# AMU-S04-V00-Microcontroller.net
KiCad netlist of a schematic drawn in Altium Designer
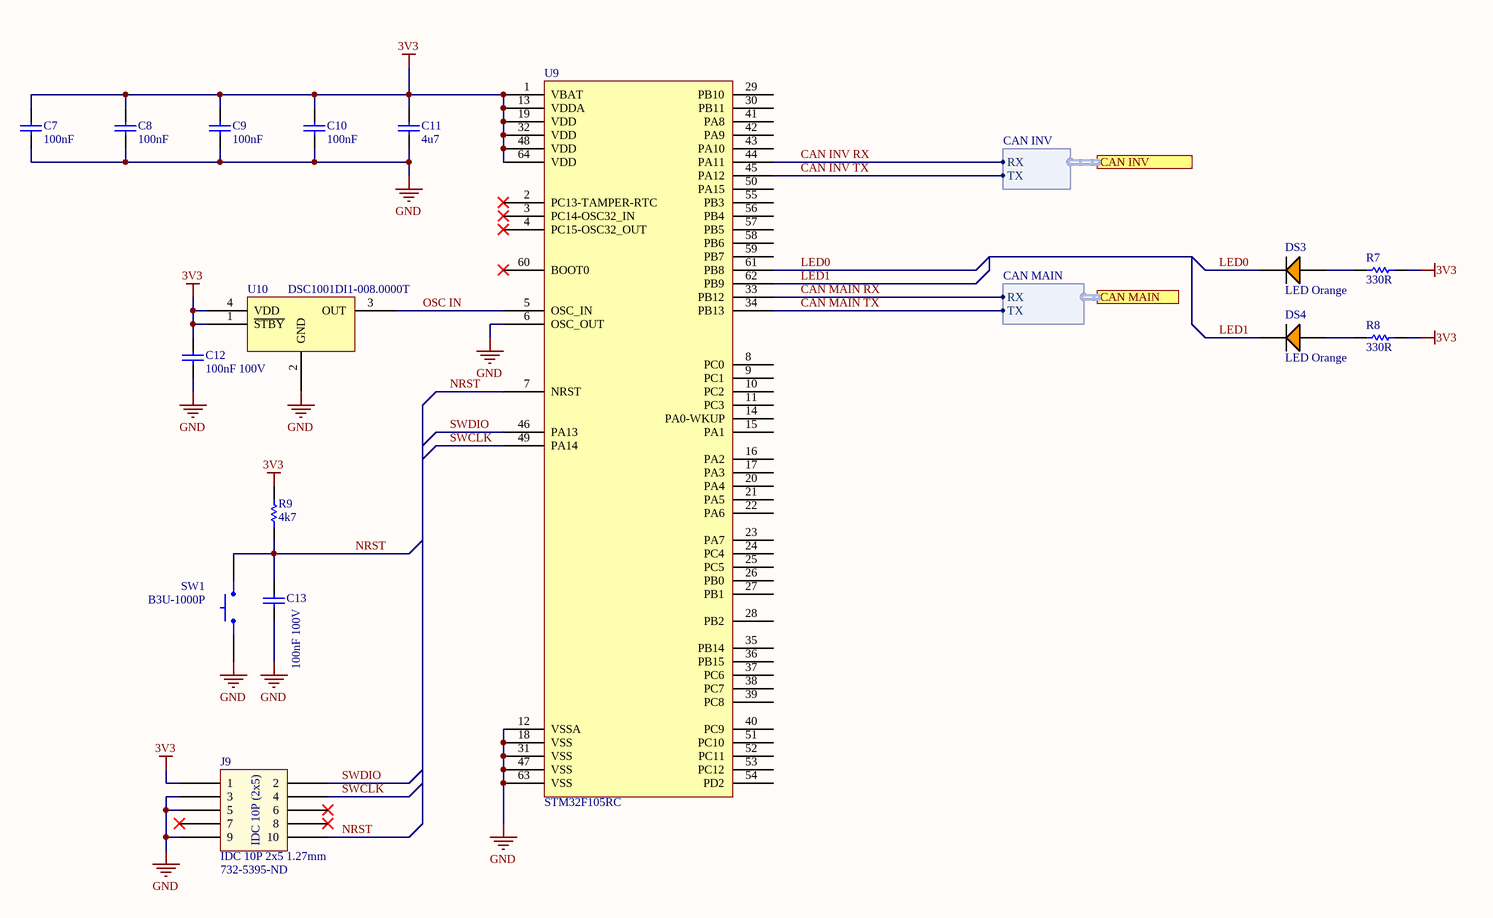
[diagram p0: AMU-S04-V00-Microcontroller.SchDoc]

(export (version "E")
  (design (tool "Eeschema 10.0.6"))
  (components
    (comp (ref "C7")
      (value "100nF")
      (footprint "Cap_Ceramic_0603")
      (description "Capacitor, Ceramic, SMD, 100nF, 50V, 5%, X7R, 0603")
      (libsource (lib "StandardCapacitors") (part "100nF 50V 5% X7R 0603"))
    )
    (comp (ref "C8")
      (value "100nF")
      (footprint "Cap_Ceramic_0603")
      (description "Capacitor, Ceramic, SMD, 100nF, 50V, 5%, X7R, 0603")
      (libsource (lib "StandardCapacitors") (part "100nF 50V 5% X7R 0603"))
    )
    (comp (ref "C9")
      (value "100nF")
      (footprint "Cap_Ceramic_0603")
      (description "Capacitor, Ceramic, SMD, 100nF, 50V, 5%, X7R, 0603")
      (libsource (lib "StandardCapacitors") (part "100nF 50V 5% X7R 0603"))
    )
    (comp (ref "C10")
      (value "100nF")
      (footprint "Cap_Ceramic_0603")
      (description "Capacitor, Ceramic, SMD, 100nF, 50V, 5%, X7R, 0603")
      (libsource (lib "StandardCapacitors") (part "100nF 50V 5% X7R 0603"))
    )
    (comp (ref "C11")
      (value "4u7")
      (footprint "Cap_Ceramic_0603")
      (description "Capacitor, Ceramic, SMD, 4u7, 50V, 5%, X7R, 0603")
      (libsource (lib "StandardCapacitors") (part "4u7 50V 5% X7R 0603"))
    )
    (comp (ref "C12")
      (value "100nF 100V")
      (footprint "Cap_Ceramic_0603")
      (description "Capacitor, Ceramic, SMD, 100nF, 100V, 5%, X7R, 0603")
      (libsource (lib "StandardCapacitors") (part "100nF 100V 5% X7R 0603"))
    )
    (comp (ref "C13")
      (value "100nF 100V")
      (footprint "Cap_Ceramic_0603")
      (description "Capacitor, Ceramic, SMD, 100nF, 100V, 5%, X7R, 0603")
      (libsource (lib "StandardCapacitors") (part "100nF 100V 5% X7R 0603"))
    )
    (comp (ref "DS3")
      (value "LED Orange")
      (footprint "LED ORANGE 0603")
      (libsource (lib "QUTMS_LEDLibrary") (part "LED ORANGE 0603"))
    )
    (comp (ref "DS4")
      (value "LED Orange")
      (footprint "LED ORANGE 0603")
      (libsource (lib "QUTMS_LEDLibrary") (part "LED ORANGE 0603"))
    )
    (comp (ref "J9")
      (value "IDC 10P 2x5 1.27mm")
      (footprint "IDC 1.27MM 10P")
      (libsource (lib "IDCConnectors") (part "IDC 10P 2x5 1.27mm"))
    )
    (comp (ref "R7")
      (value "330R")
      (footprint "Res_ThinFilm_0603")
      (description "Resistor, SMD, 330R, 0.1W, 5%, 0603")
      (libsource (lib "StandardResistors") (part "330R 5% 0603"))
    )
    (comp (ref "R8")
      (value "330R")
      (footprint "Res_ThinFilm_0603")
      (description "Resistor, SMD, 330R, 0.1W, 5%, 0603")
      (libsource (lib "StandardResistors") (part "330R 5% 0603"))
    )
    (comp (ref "R9")
      (value "4k7")
      (footprint "Res_ThinFilm_0603")
      (description "Resistor, SMD, 4k7, 0.1W, 5%, 0603")
      (libsource (lib "StandardResistors") (part "4k7 5% 0603"))
    )
    (comp (ref "SW1")
      (value "B3U-1000P")
      (footprint "BTN B3U-1000P")
      (description "Omron B3U-1000P Ultra Miniture Switch")
      (libsource (lib "QUTMS_SwitchLibrary") (part "BTN B3U-1000P"))
    )
    (comp (ref "U9")
      (value "STM32F105RC")
      (footprint "STM32F105RC")
      (description "ARM® Cortex®-M3 STM32F1 Microcontroller IC 32-Bit 72MHz 256KB (256K x 8) FLASH 64-LQFP (10x10)")
      (libsource (lib "QUTMS_STM32Library") (part "STM32F105RC"))
    )
    (comp (ref "U10")
      (value "DSC1001DI1-008.0000T")
      (footprint "DSC1001DI1-008.0000TCT-ND")
      (description "on 8MHz XO (Standard) CMOS Oscillator 1.8 ~ 3.3V Standby (Power Down) 4-SMD, No Lead")
      (libsource (lib "QUTMS_CrystalLibrary") (part "DSC1001DI1-008.0000T"))
    )
  )
  (nets
    (net (code "4") (name "/CAN INV RX") (class "Default")
      (node (ref "U9") (pin "44") (pinfunction "PA11_44") (pintype "passive"))
    )
    (net (code "5") (name "/CAN INV TX") (class "Default")
      (node (ref "U9") (pin "45") (pinfunction "PA12_45") (pintype "passive"))
    )
    (net (code "6") (name "/CAN MAIN RX") (class "Default")
      (node (ref "U9") (pin "33") (pinfunction "PB12_33") (pintype "passive"))
    )
    (net (code "7") (name "/CAN MAIN TX") (class "Default")
      (node (ref "U9") (pin "34") (pinfunction "PB13_34") (pintype "passive"))
    )
    (net (code "8") (name "/LED0") (class "Default")
      (node (ref "DS3") (pin "2") (pinfunction "C_2") (pintype "passive"))
      (node (ref "U9") (pin "61") (pinfunction "PB8_61") (pintype "passive"))
    )
    (net (code "9") (name "/LED1") (class "Default")
      (node (ref "DS4") (pin "2") (pinfunction "C_2") (pintype "passive"))
      (node (ref "U9") (pin "62") (pinfunction "PB9_62") (pintype "passive"))
    )
    (net (code "10") (name "/NRST") (class "Default")
      (node (ref "C13") (pin "2") (pinfunction "2_2") (pintype "passive"))
      (node (ref "J9") (pin "10") (pinfunction "10_10") (pintype "passive"))
      (node (ref "R9") (pin "1") (pinfunction "1_1") (pintype "passive"))
      (node (ref "SW1") (pin "2") (pinfunction "2_2") (pintype "passive"))
      (node (ref "U9") (pin "7") (pinfunction "NRST_7") (pintype "passive"))
    )
    (net (code "11") (name "/OSC IN") (class "Default")
      (node (ref "U10") (pin "3") (pinfunction "OUT_3") (pintype "passive"))
      (node (ref "U9") (pin "5") (pinfunction "OSC_IN_5") (pintype "passive"))
    )
    (net (code "12") (name "/SWCLK") (class "Default")
      (node (ref "J9") (pin "4") (pinfunction "4_4") (pintype "passive"))
      (node (ref "U9") (pin "49") (pinfunction "PA14_49") (pintype "passive"))
    )
    (net (code "13") (name "/SWDIO") (class "Default")
      (node (ref "J9") (pin "2") (pinfunction "2_2") (pintype "passive"))
      (node (ref "U9") (pin "46") (pinfunction "PA13_46") (pintype "passive"))
    )
    (net (code "16") (name "3V3") (class "Default")
      (node (ref "C10") (pin "2") (pinfunction "2_2") (pintype "passive"))
      (node (ref "C11") (pin "2") (pinfunction "2_2") (pintype "passive"))
      (node (ref "C12") (pin "2") (pinfunction "2_2") (pintype "passive"))
      (node (ref "C7") (pin "2") (pinfunction "2_2") (pintype "passive"))
      (node (ref "C8") (pin "2") (pinfunction "2_2") (pintype "passive"))
      (node (ref "C9") (pin "2") (pinfunction "2_2") (pintype "passive"))
      (node (ref "J9") (pin "1") (pinfunction "1_1") (pintype "passive"))
      (node (ref "R7") (pin "2") (pinfunction "2_2") (pintype "passive"))
      (node (ref "R8") (pin "2") (pinfunction "2_2") (pintype "passive"))
      (node (ref "R9") (pin "2") (pinfunction "2_2") (pintype "passive"))
      (node (ref "U10") (pin "1") (pinfunction "~{STBY}_1") (pintype "passive"))
      (node (ref "U10") (pin "4") (pinfunction "VDD_4") (pintype "passive"))
      (node (ref "U9") (pin "1") (pinfunction "VBAT_1") (pintype "passive"))
      (node (ref "U9") (pin "13") (pinfunction "VDDA_13") (pintype "passive"))
      (node (ref "U9") (pin "19") (pinfunction "VDD_19") (pintype "passive"))
      (node (ref "U9") (pin "32") (pinfunction "VDD_32") (pintype "passive"))
      (node (ref "U9") (pin "48") (pinfunction "VDD_48") (pintype "passive"))
      (node (ref "U9") (pin "64") (pinfunction "VDD_64") (pintype "passive"))
    )
    (net (code "17") (name "GND") (class "Default")
      (node (ref "C10") (pin "1") (pinfunction "1_1") (pintype "passive"))
      (node (ref "C11") (pin "1") (pinfunction "1_1") (pintype "passive"))
      (node (ref "C12") (pin "1") (pinfunction "1_1") (pintype "passive"))
      (node (ref "C13") (pin "1") (pinfunction "1_1") (pintype "passive"))
      (node (ref "C7") (pin "1") (pinfunction "1_1") (pintype "passive"))
      (node (ref "C8") (pin "1") (pinfunction "1_1") (pintype "passive"))
      (node (ref "C9") (pin "1") (pinfunction "1_1") (pintype "passive"))
      (node (ref "J9") (pin "3") (pinfunction "3_3") (pintype "passive"))
      (node (ref "J9") (pin "5") (pinfunction "5_5") (pintype "passive"))
      (node (ref "J9") (pin "9") (pinfunction "9_9") (pintype "passive"))
      (node (ref "SW1") (pin "1") (pinfunction "1_1") (pintype "passive"))
      (node (ref "U10") (pin "2") (pinfunction "GND_2") (pintype "passive"))
      (node (ref "U9") (pin "12") (pinfunction "VSSA_12") (pintype "passive"))
      (node (ref "U9") (pin "18") (pinfunction "VSS_18") (pintype "passive"))
      (node (ref "U9") (pin "31") (pinfunction "VSS_31") (pintype "passive"))
      (node (ref "U9") (pin "47") (pinfunction "VSS_47") (pintype "passive"))
      (node (ref "U9") (pin "6") (pinfunction "OSC_OUT_6") (pintype "passive"))
      (node (ref "U9") (pin "63") (pinfunction "VSS_63") (pintype "passive"))
    )
    (net (code "18") (name "Net-(DS3-A)") (class "Default")
      (node (ref "DS3") (pin "1") (pinfunction "A_1") (pintype "passive"))
      (node (ref "R7") (pin "1") (pinfunction "1_1") (pintype "passive"))
    )
    (net (code "19") (name "Net-(DS4-A)") (class "Default")
      (node (ref "DS4") (pin "1") (pinfunction "A_1") (pintype "passive"))
      (node (ref "R8") (pin "1") (pinfunction "1_1") (pintype "passive"))
    )
    (net (code "20") (name "unconnected-(J9-Pad6)") (class "Default")
      (node (ref "J9") (pin "6") (pinfunction "6_6") (pintype "passive+no_connect"))
    )
    (net (code "21") (name "unconnected-(J9-Pad7)") (class "Default")
      (node (ref "J9") (pin "7") (pinfunction "7_7") (pintype "passive+no_connect"))
    )
    (net (code "22") (name "unconnected-(J9-Pad8)") (class "Default")
      (node (ref "J9") (pin "8") (pinfunction "8_8") (pintype "passive+no_connect"))
    )
    (net (code "23") (name "unconnected-(U9-BOOT0-Pad60)") (class "Default")
      (node (ref "U9") (pin "60") (pinfunction "BOOT0_60") (pintype "passive+no_connect"))
    )
    (net (code "24") (name "unconnected-(U9-PA0-WKUP-Pad14)") (class "Default")
      (node (ref "U9") (pin "14") (pinfunction "PA0-WKUP_14") (pintype "passive"))
    )
    (net (code "25") (name "unconnected-(U9-PA1-Pad15)") (class "Default")
      (node (ref "U9") (pin "15") (pinfunction "PA1_15") (pintype "passive"))
    )
    (net (code "26") (name "unconnected-(U9-PA2-Pad16)") (class "Default")
      (node (ref "U9") (pin "16") (pinfunction "PA2_16") (pintype "passive"))
    )
    (net (code "27") (name "unconnected-(U9-PA3-Pad17)") (class "Default")
      (node (ref "U9") (pin "17") (pinfunction "PA3_17") (pintype "passive"))
    )
    (net (code "28") (name "unconnected-(U9-PA4-Pad20)") (class "Default")
      (node (ref "U9") (pin "20") (pinfunction "PA4_20") (pintype "passive"))
    )
    (net (code "29") (name "unconnected-(U9-PA5-Pad21)") (class "Default")
      (node (ref "U9") (pin "21") (pinfunction "PA5_21") (pintype "passive"))
    )
    (net (code "30") (name "unconnected-(U9-PA6-Pad22)") (class "Default")
      (node (ref "U9") (pin "22") (pinfunction "PA6_22") (pintype "passive"))
    )
    (net (code "31") (name "unconnected-(U9-PA7-Pad23)") (class "Default")
      (node (ref "U9") (pin "23") (pinfunction "PA7_23") (pintype "passive"))
    )
    (net (code "32") (name "unconnected-(U9-PA8-Pad41)") (class "Default")
      (node (ref "U9") (pin "41") (pinfunction "PA8_41") (pintype "passive"))
    )
    (net (code "33") (name "unconnected-(U9-PA9-Pad42)") (class "Default")
      (node (ref "U9") (pin "42") (pinfunction "PA9_42") (pintype "passive"))
    )
    (net (code "34") (name "unconnected-(U9-PA10-Pad43)") (class "Default")
      (node (ref "U9") (pin "43") (pinfunction "PA10_43") (pintype "passive"))
    )
    (net (code "35") (name "unconnected-(U9-PA15-Pad50)") (class "Default")
      (node (ref "U9") (pin "50") (pinfunction "PA15_50") (pintype "passive"))
    )
    (net (code "36") (name "unconnected-(U9-PB0-Pad26)") (class "Default")
      (node (ref "U9") (pin "26") (pinfunction "PB0_26") (pintype "passive"))
    )
    (net (code "37") (name "unconnected-(U9-PB1-Pad27)") (class "Default")
      (node (ref "U9") (pin "27") (pinfunction "PB1_27") (pintype "passive"))
    )
    (net (code "38") (name "unconnected-(U9-PB2-Pad28)") (class "Default")
      (node (ref "U9") (pin "28") (pinfunction "PB2_28") (pintype "passive"))
    )
    (net (code "39") (name "unconnected-(U9-PB3-Pad55)") (class "Default")
      (node (ref "U9") (pin "55") (pinfunction "PB3_55") (pintype "passive"))
    )
    (net (code "40") (name "unconnected-(U9-PB4-Pad56)") (class "Default")
      (node (ref "U9") (pin "56") (pinfunction "PB4_56") (pintype "passive"))
    )
    (net (code "41") (name "unconnected-(U9-PB5-Pad57)") (class "Default")
      (node (ref "U9") (pin "57") (pinfunction "PB5_57") (pintype "passive"))
    )
    (net (code "42") (name "unconnected-(U9-PB6-Pad58)") (class "Default")
      (node (ref "U9") (pin "58") (pinfunction "PB6_58") (pintype "passive"))
    )
    (net (code "43") (name "unconnected-(U9-PB7-Pad59)") (class "Default")
      (node (ref "U9") (pin "59") (pinfunction "PB7_59") (pintype "passive"))
    )
    (net (code "44") (name "unconnected-(U9-PB10-Pad29)") (class "Default")
      (node (ref "U9") (pin "29") (pinfunction "PB10_29") (pintype "passive"))
    )
    (net (code "45") (name "unconnected-(U9-PB11-Pad30)") (class "Default")
      (node (ref "U9") (pin "30") (pinfunction "PB11_30") (pintype "passive"))
    )
    (net (code "46") (name "unconnected-(U9-PB14-Pad35)") (class "Default")
      (node (ref "U9") (pin "35") (pinfunction "PB14_35") (pintype "passive"))
    )
    (net (code "47") (name "unconnected-(U9-PB15-Pad36)") (class "Default")
      (node (ref "U9") (pin "36") (pinfunction "PB15_36") (pintype "passive"))
    )
    (net (code "48") (name "unconnected-(U9-PC0-Pad8)") (class "Default")
      (node (ref "U9") (pin "8") (pinfunction "PC0_8") (pintype "passive"))
    )
    (net (code "49") (name "unconnected-(U9-PC1-Pad9)") (class "Default")
      (node (ref "U9") (pin "9") (pinfunction "PC1_9") (pintype "passive"))
    )
    (net (code "50") (name "unconnected-(U9-PC2-Pad10)") (class "Default")
      (node (ref "U9") (pin "10") (pinfunction "PC2_10") (pintype "passive"))
    )
    (net (code "51") (name "unconnected-(U9-PC3-Pad11)") (class "Default")
      (node (ref "U9") (pin "11") (pinfunction "PC3_11") (pintype "passive"))
    )
    (net (code "52") (name "unconnected-(U9-PC4-Pad24)") (class "Default")
      (node (ref "U9") (pin "24") (pinfunction "PC4_24") (pintype "passive"))
    )
    (net (code "53") (name "unconnected-(U9-PC5-Pad25)") (class "Default")
      (node (ref "U9") (pin "25") (pinfunction "PC5_25") (pintype "passive"))
    )
    (net (code "54") (name "unconnected-(U9-PC6-Pad37)") (class "Default")
      (node (ref "U9") (pin "37") (pinfunction "PC6_37") (pintype "passive"))
    )
    (net (code "55") (name "unconnected-(U9-PC7-Pad38)") (class "Default")
      (node (ref "U9") (pin "38") (pinfunction "PC7_38") (pintype "passive"))
    )
    (net (code "56") (name "unconnected-(U9-PC8-Pad39)") (class "Default")
      (node (ref "U9") (pin "39") (pinfunction "PC8_39") (pintype "passive"))
    )
    (net (code "57") (name "unconnected-(U9-PC9-Pad40)") (class "Default")
      (node (ref "U9") (pin "40") (pinfunction "PC9_40") (pintype "passive"))
    )
    (net (code "58") (name "unconnected-(U9-PC10-Pad51)") (class "Default")
      (node (ref "U9") (pin "51") (pinfunction "PC10_51") (pintype "passive"))
    )
    (net (code "59") (name "unconnected-(U9-PC11-Pad52)") (class "Default")
      (node (ref "U9") (pin "52") (pinfunction "PC11_52") (pintype "passive"))
    )
    (net (code "60") (name "unconnected-(U9-PC12-Pad53)") (class "Default")
      (node (ref "U9") (pin "53") (pinfunction "PC12_53") (pintype "passive"))
    )
    (net (code "61") (name "unconnected-(U9-PC13-TAMPER-RTC-Pad2)") (class "Default")
      (node (ref "U9") (pin "2") (pinfunction "PC13-TAMPER-RTC_2") (pintype "passive+no_connect"))
    )
    (net (code "62") (name "unconnected-(U9-PC14-OSC32_IN-Pad3)") (class "Default")
      (node (ref "U9") (pin "3") (pinfunction "PC14-OSC32_IN_3") (pintype "passive+no_connect"))
    )
    (net (code "63") (name "unconnected-(U9-PC15-OSC32_OUT-Pad4)") (class "Default")
      (node (ref "U9") (pin "4") (pinfunction "PC15-OSC32_OUT_4") (pintype "passive+no_connect"))
    )
    (net (code "64") (name "unconnected-(U9-PD2-Pad54)") (class "Default")
      (node (ref "U9") (pin "54") (pinfunction "PD2_54") (pintype "passive"))
    )
  )
)
